# power.net
KiCad netlist of a schematic drawn in Altium Designer
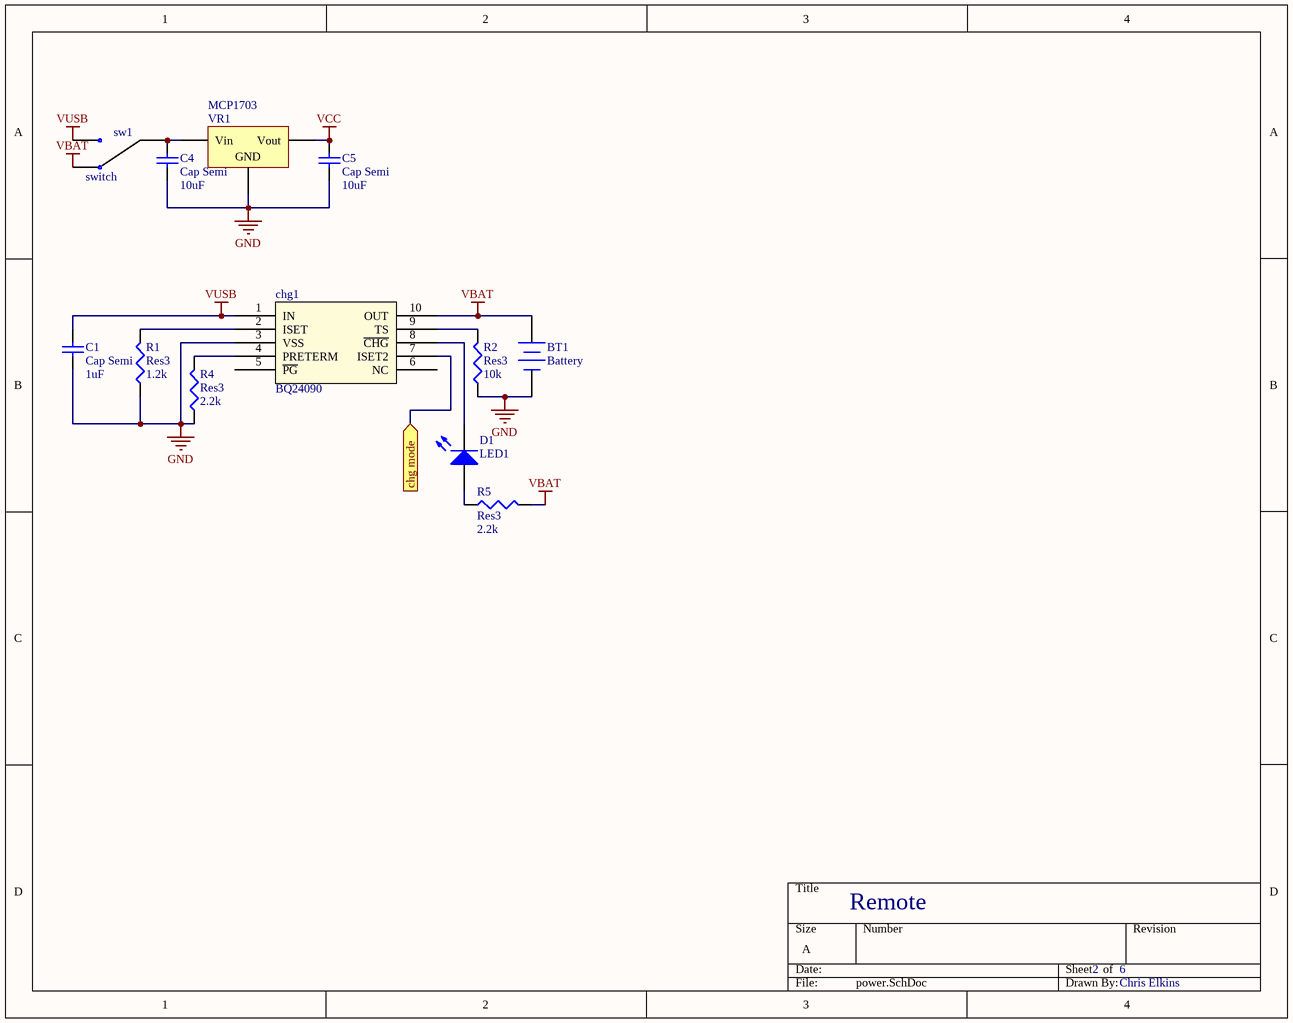
[diagram p0: power.SchDoc]

(export (version "E")
  (design (tool "Eeschema 10.0.6"))
  (components
    (comp (ref "BT1")
      (value "Battery")
      (footprint "BAT-2")
      (description "Multicell Battery")
      (fields (field (name "PUBLISHER") "Altium Limited"))
      (libsource (lib "Miscellaneous Devices") (part "Battery"))
    )
    (comp (ref "C1")
      (value "Cap Semi")
      (footprint "CAPC1608L")
      (description "Capacitor (Semiconductor SIM Model)")
      (fields (field (name "ALTIUM_VALUE") "1uF") (field (name "PUBLISHER") "Altium Limited"))
      (libsource (lib "Miscellaneous Devices") (part "Cap Semi"))
    )
    (comp (ref "C4")
      (value "Cap Semi")
      (footprint "CAPC1608L")
      (description "Capacitor (Semiconductor SIM Model)")
      (fields (field (name "ALTIUM_VALUE") "10uF") (field (name "PUBLISHER") "Altium Limited"))
      (libsource (lib "Miscellaneous Devices") (part "Cap Semi"))
    )
    (comp (ref "C5")
      (value "Cap Semi")
      (footprint "CAPC1608L")
      (description "Capacitor (Semiconductor SIM Model)")
      (fields (field (name "ALTIUM_VALUE") "10uF") (field (name "PUBLISHER") "Altium Limited"))
      (libsource (lib "Miscellaneous Devices") (part "Cap Semi"))
    )
    (comp (ref "chg1")
      (value "BQ24090")
      (footprint "mSOP10")
      (description "Li+ battery charger")
      (libsource (lib "Integrated_Library1") (part "BQ24090"))
    )
    (comp (ref "D1")
      (value "LED1")
      (footprint "LED-1")
      (description "Typical RED GaAs LED")
      (fields (field (name "PUBLISHER") "Altium Limited"))
      (libsource (lib "Miscellaneous Devices") (part "LED1"))
    )
    (comp (ref "R1")
      (value "Res3")
      (footprint "RESC1608L")
      (description "Resistor")
      (fields (field (name "ALTIUM_VALUE") "1.2k") (field (name "PUBLISHER") "Altium Limited"))
      (libsource (lib "Miscellaneous Devices") (part "Res3"))
    )
    (comp (ref "R2")
      (value "Res3")
      (footprint "RESC1608L")
      (description "Resistor")
      (fields (field (name "ALTIUM_VALUE") "10k") (field (name "PUBLISHER") "Altium Limited"))
      (libsource (lib "Miscellaneous Devices") (part "Res3"))
    )
    (comp (ref "R4")
      (value "Res3")
      (footprint "RESC1608L")
      (description "Resistor")
      (fields (field (name "ALTIUM_VALUE") "2.2k") (field (name "PUBLISHER") "Altium Limited"))
      (libsource (lib "Miscellaneous Devices") (part "Res3"))
    )
    (comp (ref "R5")
      (value "Res3")
      (footprint "RESC1608L")
      (description "Resistor")
      (fields (field (name "ALTIUM_VALUE") "2.2k") (field (name "PUBLISHER") "Altium Limited"))
      (libsource (lib "Miscellaneous Devices") (part "Res3"))
    )
    (comp (ref "sw1")
      (value "switch")
      (footprint "switch")
      (libsource (lib "Integrated_Library1") (part "switch"))
    )
    (comp (ref "VR1")
      (value "MCP1703")
      (footprint "SOT223-4N")
      (description "Voltage Regulator")
      (fields (field (name "PUBLISHER") "Altium Limited"))
      (libsource (lib "Miscellaneous Devices") (part "Volt Reg"))
    )
  )
  (nets
    (net (code "1") (name "/chg mode") (class "Default")
      (node (ref "chg1") (pin "7") (pinfunction "ISET2_7") (pintype "passive"))
    )
    (net (code "2") (name "GND") (class "Default")
      (node (ref "BT1") (pin "2") (pinfunction "-_2") (pintype "passive"))
      (node (ref "C1") (pin "1") (pinfunction "1_1") (pintype "passive"))
      (node (ref "C4") (pin "1") (pinfunction "1_1") (pintype "passive"))
      (node (ref "C5") (pin "1") (pinfunction "1_1") (pintype "passive"))
      (node (ref "R1") (pin "1") (pinfunction "1_1") (pintype "passive"))
      (node (ref "R2") (pin "1") (pinfunction "1_1") (pintype "passive"))
      (node (ref "R4") (pin "1") (pinfunction "1_1") (pintype "passive"))
      (node (ref "VR1") (pin "2") (pinfunction "GND_2") (pintype "passive"))
      (node (ref "chg1") (pin "3") (pinfunction "VSS_3") (pintype "passive"))
    )
    (net (code "3") (name "Net-(D1-A)") (class "Default")
      (node (ref "D1") (pin "1") (pinfunction "A_1") (pintype "passive"))
      (node (ref "R5") (pin "1") (pinfunction "1_1") (pintype "passive"))
    )
    (net (code "4") (name "Net-(D1-K)") (class "Default")
      (node (ref "D1") (pin "2") (pinfunction "K_2") (pintype "passive"))
      (node (ref "chg1") (pin "8") (pinfunction "~{CHG}_8") (pintype "passive"))
    )
    (net (code "5") (name "Net-(VR1-Vin)") (class "Default")
      (node (ref "C4") (pin "2") (pinfunction "2_2") (pintype "passive"))
      (node (ref "VR1") (pin "1") (pinfunction "Vin_1") (pintype "passive"))
      (node (ref "sw1") (pin "2") (pinfunction "29_2") (pintype "passive"))
    )
    (net (code "6") (name "Net-(chg1-ISET)") (class "Default")
      (node (ref "R1") (pin "2") (pinfunction "2_2") (pintype "passive"))
      (node (ref "chg1") (pin "2") (pinfunction "ISET_2") (pintype "passive"))
    )
    (net (code "7") (name "Net-(chg1-PRETERM)") (class "Default")
      (node (ref "R4") (pin "2") (pinfunction "2_2") (pintype "passive"))
      (node (ref "chg1") (pin "4") (pinfunction "PRETERM_4") (pintype "passive"))
    )
    (net (code "8") (name "Net-(chg1-TS)") (class "Default")
      (node (ref "R2") (pin "2") (pinfunction "2_2") (pintype "passive"))
      (node (ref "chg1") (pin "9") (pinfunction "TS_9") (pintype "passive"))
    )
    (net (code "9") (name "VBAT") (class "Default")
      (node (ref "BT1") (pin "1") (pinfunction "+_1") (pintype "passive"))
      (node (ref "R5") (pin "2") (pinfunction "2_2") (pintype "passive"))
      (node (ref "chg1") (pin "10") (pinfunction "OUT_10") (pintype "passive"))
      (node (ref "sw1") (pin "1") (pinfunction "1_1") (pintype "passive"))
    )
    (net (code "10") (name "VCC") (class "Default")
      (node (ref "C5") (pin "2") (pinfunction "2_2") (pintype "passive"))
      (node (ref "VR1") (pin "3") (pinfunction "Vout_3") (pintype "passive"))
    )
    (net (code "11") (name "VUSB") (class "Default")
      (node (ref "C1") (pin "2") (pinfunction "2_2") (pintype "passive"))
      (node (ref "chg1") (pin "1") (pinfunction "IN_1") (pintype "passive"))
      (node (ref "sw1") (pin "3") (pinfunction "3_3") (pintype "passive"))
    )
    (net (code "12") (name "unconnected-(chg1-NC-Pad6)") (class "Default")
      (node (ref "chg1") (pin "6") (pinfunction "NC_6") (pintype "passive"))
    )
    (net (code "13") (name "unconnected-(chg1-~{PG}-Pad5)") (class "Default")
      (node (ref "chg1") (pin "5") (pinfunction "~{PG}_5") (pintype "passive"))
    )
  )
)
